# CP3.net
KiCad netlist of a schematic drawn in EAGLE
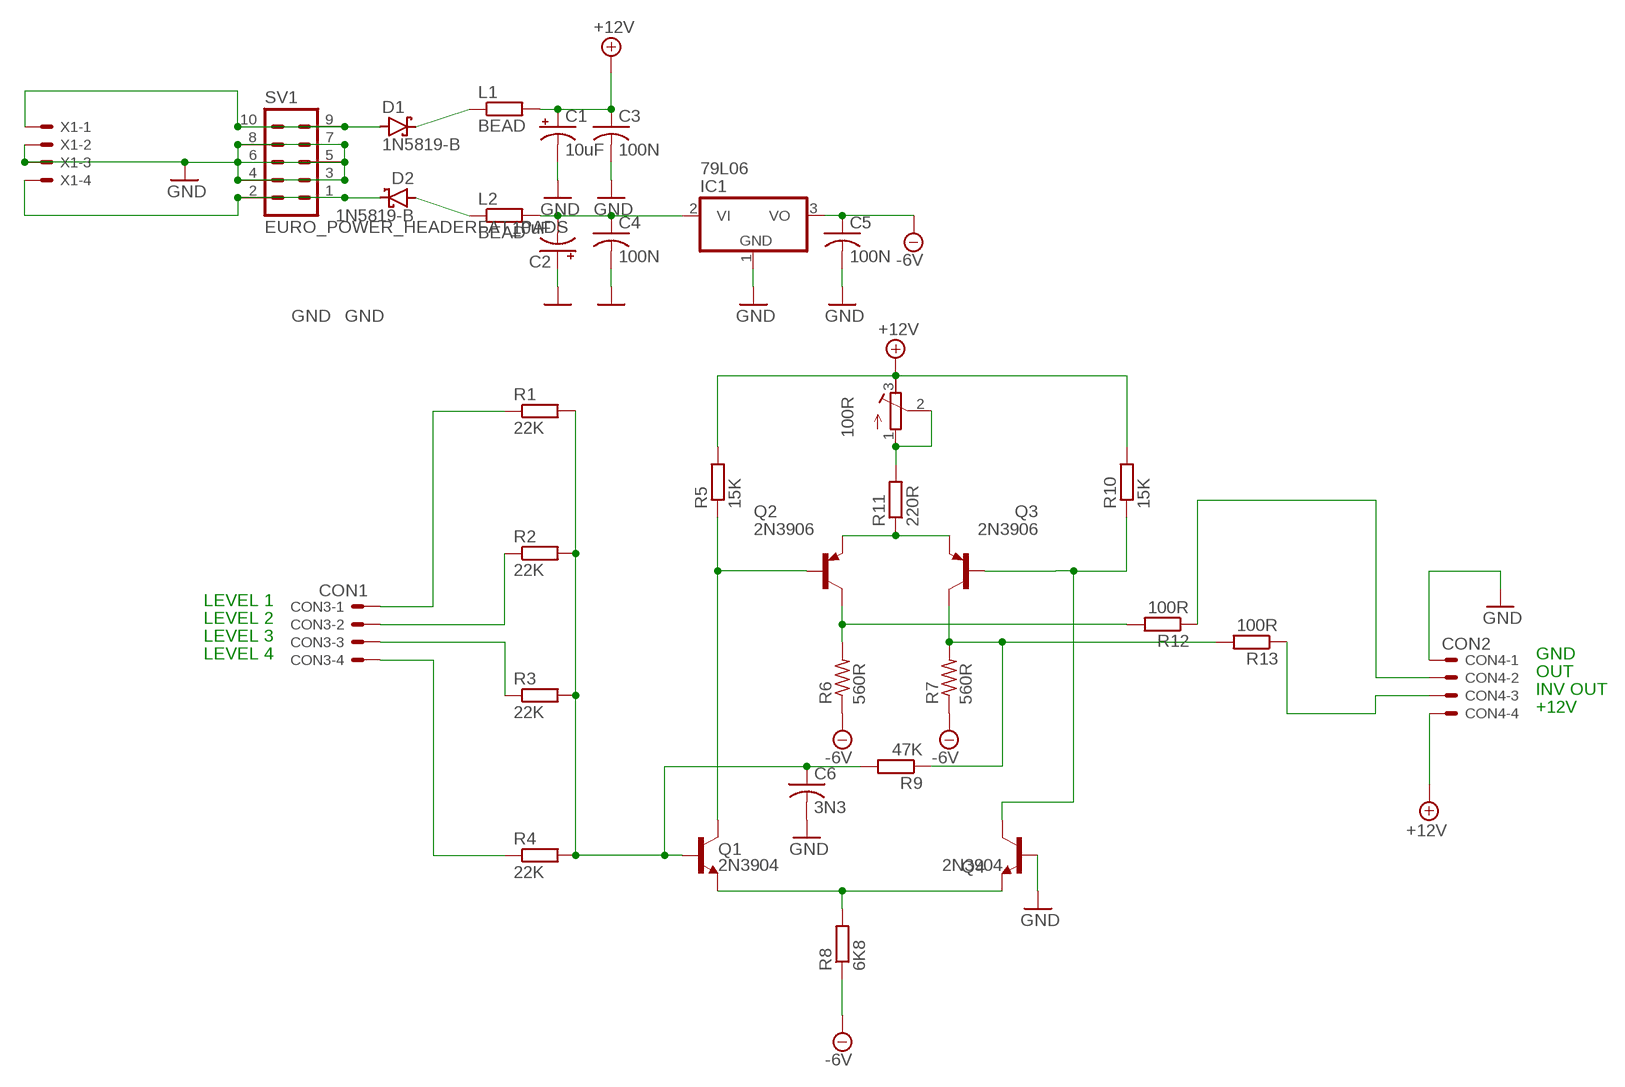
[diagram p0: schematic, sheet 1]

(export (version "E")
  (design (tool "Eeschema 10.0.6"))
  (components
    (comp (ref "100R")
      (value "R-TRIMM3296W")
      (footprint "eagle-import:RTRIM3296W")
      (libsource (lib "eagle-import") (part "R-TRIMM3296W"))
    )
    (comp (ref "C1")
      (value "10uF")
      (footprint "eagle-import:E2,5-7")
      (libsource (lib "eagle-import") (part "CPOL-USE2.5-7"))
    )
    (comp (ref "C2")
      (value "10uF")
      (footprint "eagle-import:E2,5-7")
      (libsource (lib "eagle-import") (part "CPOL-USE2.5-7"))
    )
    (comp (ref "C3")
      (value "100N")
      (footprint "eagle-import:C025-025X050")
      (libsource (lib "eagle-import") (part "C-US025-025X050"))
    )
    (comp (ref "C4")
      (value "100N")
      (footprint "eagle-import:C025-025X050")
      (libsource (lib "eagle-import") (part "C-US025-025X050"))
    )
    (comp (ref "C5")
      (value "100N")
      (footprint "eagle-import:C025-025X050")
      (libsource (lib "eagle-import") (part "C-US025-025X050"))
    )
    (comp (ref "C6")
      (value "3N3")
      (footprint "eagle-import:C025-025X050")
      (libsource (lib "eagle-import") (part "C-US025-025X050"))
    )
    (comp (ref "CON3")
      (value "CON1")
      (footprint "eagle-import:22-23-2041")
      (fields (field (name "MF") "MOLEX") (field (name "MPN") "22-23-2041"))
      (libsource (lib "eagle-import") (part "22-23-2041"))
    )
    (comp (ref "CON4")
      (value "CON2")
      (footprint "eagle-import:22-23-2041")
      (fields (field (name "MF") "MOLEX") (field (name "MPN") "22-23-2041"))
      (libsource (lib "eagle-import") (part "22-23-2041"))
    )
    (comp (ref "D1")
      (value "1N5819-B")
      (footprint "eagle-import:DO41-7.6")
      (libsource (lib "eagle-import") (part "1N5819-B"))
    )
    (comp (ref "D2")
      (value "1N5819-B")
      (footprint "eagle-import:DO41-7.6")
      (libsource (lib "eagle-import") (part "1N5819-B"))
    )
    (comp (ref "IC1")
      (value "79L06")
      (footprint "eagle-import:TO92")
      (libsource (lib "eagle-import") (part "79ZL12"))
    )
    (comp (ref "L1")
      (value "BEAD")
      (footprint "eagle-import:10MM_RESISTOR")
      (libsource (lib "eagle-import") (part "RESISTOR10MM_RESISTOR"))
    )
    (comp (ref "L2")
      (value "BEAD")
      (footprint "eagle-import:10MM_RESISTOR")
      (libsource (lib "eagle-import") (part "RESISTOR10MM_RESISTOR"))
    )
    (comp (ref "Q1")
      (value "2N3904")
      (footprint "eagle-import:TO-92")
      (libsource (lib "eagle-import") (part "TRANS_NPN-2N3904"))
    )
    (comp (ref "Q2")
      (value "2N3906")
      (footprint "eagle-import:TO92")
      (libsource (lib "eagle-import") (part "2N3906"))
    )
    (comp (ref "Q3")
      (value "2N3906")
      (footprint "eagle-import:TO92")
      (libsource (lib "eagle-import") (part "2N3906"))
    )
    (comp (ref "Q4")
      (value "2N3904")
      (footprint "eagle-import:TO-92")
      (libsource (lib "eagle-import") (part "TRANS_NPN-2N3904"))
    )
    (comp (ref "R1")
      (value "22K")
      (footprint "eagle-import:10MM_RESISTOR")
      (libsource (lib "eagle-import") (part "RESISTOR10MM_RESISTOR"))
    )
    (comp (ref "R2")
      (value "22K")
      (footprint "eagle-import:10MM_RESISTOR")
      (libsource (lib "eagle-import") (part "RESISTOR10MM_RESISTOR"))
    )
    (comp (ref "R3")
      (value "22K")
      (footprint "eagle-import:10MM_RESISTOR")
      (libsource (lib "eagle-import") (part "RESISTOR10MM_RESISTOR"))
    )
    (comp (ref "R4")
      (value "22K")
      (footprint "eagle-import:10MM_RESISTOR")
      (libsource (lib "eagle-import") (part "RESISTOR10MM_RESISTOR"))
    )
    (comp (ref "R5")
      (value "15K")
      (footprint "eagle-import:10MM_RESISTOR")
      (libsource (lib "eagle-import") (part "RESISTOR10MM_RESISTOR"))
    )
    (comp (ref "R6")
      (value "560R")
      (footprint "eagle-import:0207_12")
      (libsource (lib "eagle-import") (part "R-US_0207/12"))
    )
    (comp (ref "R7")
      (value "560R")
      (footprint "eagle-import:0207_12")
      (libsource (lib "eagle-import") (part "R-US_0207/12"))
    )
    (comp (ref "R8")
      (value "6K8")
      (footprint "eagle-import:10MM_RESISTOR")
      (libsource (lib "eagle-import") (part "RESISTOR10MM_RESISTOR"))
    )
    (comp (ref "R9")
      (value "47K")
      (footprint "eagle-import:10MM_RESISTOR")
      (libsource (lib "eagle-import") (part "RESISTOR10MM_RESISTOR"))
    )
    (comp (ref "R10")
      (value "15K")
      (footprint "eagle-import:10MM_RESISTOR")
      (libsource (lib "eagle-import") (part "RESISTOR10MM_RESISTOR"))
    )
    (comp (ref "R11")
      (value "220R")
      (footprint "eagle-import:10MM_RESISTOR")
      (libsource (lib "eagle-import") (part "RESISTOR10MM_RESISTOR"))
    )
    (comp (ref "R12")
      (value "100R")
      (footprint "eagle-import:10MM_RESISTOR")
      (libsource (lib "eagle-import") (part "RESISTOR10MM_RESISTOR"))
    )
    (comp (ref "R13")
      (value "100R")
      (footprint "eagle-import:10MM_RESISTOR")
      (libsource (lib "eagle-import") (part "RESISTOR10MM_RESISTOR"))
    )
    (comp (ref "SV1")
      (value "EURO_POWER_HEADERFAT_PADS")
      (footprint "eagle-import:EURO_PWR_HEADER_FAT")
      (libsource (lib "eagle-import") (part "EURO_POWER_HEADERFAT_PADS"))
    )
    (comp (ref "X1")
      (value "KK-156-4")
      (footprint "eagle-import:KK-156-4")
      (fields (field (name "MF") "MOLEX"))
      (libsource (lib "eagle-import") (part "KK-156-4"))
    )
  )
  (nets
    (net (code "1") (name "+12V") (class "Default")
      (node (ref "100R") (pin "3") (pinfunction "E_3") (pintype "passive"))
      (node (ref "C1") (pin "+") (pinfunction "+_+") (pintype "passive"))
      (node (ref "C3") (pin "1") (pinfunction "1_1") (pintype "passive"))
      (node (ref "CON4") (pin "4") (pinfunction "S_4") (pintype "passive"))
      (node (ref "L1") (pin "2") (pinfunction "2_2") (pintype "passive"))
      (node (ref "R10") (pin "2") (pinfunction "2_2") (pintype "passive"))
      (node (ref "R5") (pin "2") (pinfunction "2_2") (pintype "passive"))
    )
    (net (code "2") (name "-6V") (class "Default")
      (node (ref "C5") (pin "1") (pinfunction "1_1") (pintype "passive"))
      (node (ref "IC1") (pin "3") (pinfunction "VO_3") (pintype "passive"))
      (node (ref "R6") (pin "1") (pinfunction "1_1") (pintype "passive"))
      (node (ref "R7") (pin "1") (pinfunction "1_1") (pintype "passive"))
      (node (ref "R8") (pin "1") (pinfunction "1_1") (pintype "passive"))
    )
    (net (code "3") (name "GND") (class "Default")
      (node (ref "C1") (pin "-") (pinfunction "-_-") (pintype "passive"))
      (node (ref "C2") (pin "+") (pinfunction "+_+") (pintype "passive"))
      (node (ref "C3") (pin "2") (pinfunction "2_2") (pintype "passive"))
      (node (ref "C4") (pin "2") (pinfunction "2_2") (pintype "passive"))
      (node (ref "C5") (pin "2") (pinfunction "2_2") (pintype "passive"))
      (node (ref "C6") (pin "2") (pinfunction "2_2") (pintype "passive"))
      (node (ref "CON4") (pin "1") (pinfunction "S_1") (pintype "passive"))
      (node (ref "IC1") (pin "1") (pinfunction "GND_1") (pintype "passive"))
      (node (ref "Q4") (pin "2") (pinfunction "B_2") (pintype "passive"))
      (node (ref "SV1") (pin "3") (pinfunction "3_3") (pintype "passive"))
      (node (ref "SV1") (pin "4") (pinfunction "4_4") (pintype "passive"))
      (node (ref "SV1") (pin "5") (pinfunction "5_5") (pintype "passive"))
      (node (ref "SV1") (pin "6") (pinfunction "6_6") (pintype "passive"))
      (node (ref "SV1") (pin "7") (pinfunction "7_7") (pintype "passive"))
      (node (ref "SV1") (pin "8") (pinfunction "8_8") (pintype "passive"))
      (node (ref "X1") (pin "2") (pinfunction "S_2") (pintype "passive"))
      (node (ref "X1") (pin "3") (pinfunction "S_3") (pintype "passive"))
    )
    (net (code "4") (name "Net-(100R-A)") (class "Default")
      (node (ref "100R") (pin "1") (pinfunction "A_1") (pintype "passive"))
      (node (ref "100R") (pin "2") (pinfunction "S_2") (pintype "passive"))
      (node (ref "R11") (pin "2") (pinfunction "2_2") (pintype "passive"))
    )
    (net (code "5") (name "Net-(CON3A-S)") (class "Default")
      (node (ref "CON3") (pin "1") (pinfunction "S_1") (pintype "passive"))
      (node (ref "R1") (pin "1") (pinfunction "1_1") (pintype "passive"))
    )
    (net (code "6") (name "Net-(CON3B-S)") (class "Default")
      (node (ref "CON3") (pin "2") (pinfunction "S_2") (pintype "passive"))
      (node (ref "R2") (pin "1") (pinfunction "1_1") (pintype "passive"))
    )
    (net (code "7") (name "Net-(CON3C-S)") (class "Default")
      (node (ref "CON3") (pin "3") (pinfunction "S_3") (pintype "passive"))
      (node (ref "R3") (pin "1") (pinfunction "1_1") (pintype "passive"))
    )
    (net (code "8") (name "Net-(CON3D-S)") (class "Default")
      (node (ref "CON3") (pin "4") (pinfunction "S_4") (pintype "passive"))
      (node (ref "R4") (pin "1") (pinfunction "1_1") (pintype "passive"))
    )
    (net (code "9") (name "Net-(CON4B-S)") (class "Default")
      (node (ref "CON4") (pin "2") (pinfunction "S_2") (pintype "passive"))
      (node (ref "R12") (pin "1") (pinfunction "1_1") (pintype "passive"))
    )
    (net (code "10") (name "Net-(CON4C-S)") (class "Default")
      (node (ref "CON4") (pin "3") (pinfunction "S_3") (pintype "passive"))
      (node (ref "R13") (pin "1") (pinfunction "1_1") (pintype "passive"))
    )
    (net (code "11") (name "Net-(D1-PadC)") (class "Default")
      (node (ref "D1") (pin "C") (pinfunction "C_C") (pintype "passive"))
      (node (ref "L1") (pin "1") (pinfunction "1_1") (pintype "passive"))
    )
    (net (code "12") (name "Net-(D2-PadA)") (class "Default")
      (node (ref "D2") (pin "A") (pinfunction "A_A") (pintype "passive"))
      (node (ref "L2") (pin "1") (pinfunction "1_1") (pintype "passive"))
    )
    (net (code "13") (name "Net-(IC1-VI)") (class "Default")
      (node (ref "C2") (pin "-") (pinfunction "-_-") (pintype "passive"))
      (node (ref "C4") (pin "1") (pinfunction "1_1") (pintype "passive"))
      (node (ref "IC1") (pin "2") (pinfunction "VI_2") (pintype "input"))
      (node (ref "L2") (pin "2") (pinfunction "2_2") (pintype "passive"))
    )
    (net (code "14") (name "Net-(Q1-B)") (class "Default")
      (node (ref "C6") (pin "1") (pinfunction "1_1") (pintype "passive"))
      (node (ref "Q1") (pin "2") (pinfunction "B_2") (pintype "passive"))
      (node (ref "R1") (pin "2") (pinfunction "2_2") (pintype "passive"))
      (node (ref "R2") (pin "2") (pinfunction "2_2") (pintype "passive"))
      (node (ref "R3") (pin "2") (pinfunction "2_2") (pintype "passive"))
      (node (ref "R4") (pin "2") (pinfunction "2_2") (pintype "passive"))
      (node (ref "R9") (pin "2") (pinfunction "2_2") (pintype "passive"))
    )
    (net (code "15") (name "Net-(Q1-C)") (class "Default")
      (node (ref "Q1") (pin "3") (pinfunction "C_3") (pintype "passive"))
      (node (ref "Q2") (pin "2") (pinfunction "B_2") (pintype "passive"))
      (node (ref "R5") (pin "1") (pinfunction "1_1") (pintype "passive"))
    )
    (net (code "16") (name "Net-(Q1-E)") (class "Default")
      (node (ref "Q1") (pin "1") (pinfunction "E_1") (pintype "passive"))
      (node (ref "Q4") (pin "1") (pinfunction "E_1") (pintype "passive"))
      (node (ref "R8") (pin "2") (pinfunction "2_2") (pintype "passive"))
    )
    (net (code "17") (name "Net-(Q2-C)") (class "Default")
      (node (ref "Q2") (pin "1") (pinfunction "C_1") (pintype "passive"))
      (node (ref "R12") (pin "2") (pinfunction "2_2") (pintype "passive"))
      (node (ref "R6") (pin "2") (pinfunction "2_2") (pintype "passive"))
    )
    (net (code "18") (name "Net-(Q2-E)") (class "Default")
      (node (ref "Q2") (pin "3") (pinfunction "E_3") (pintype "passive"))
      (node (ref "Q3") (pin "3") (pinfunction "E_3") (pintype "passive"))
      (node (ref "R11") (pin "1") (pinfunction "1_1") (pintype "passive"))
    )
    (net (code "19") (name "Net-(Q3-B)") (class "Default")
      (node (ref "Q3") (pin "2") (pinfunction "B_2") (pintype "passive"))
      (node (ref "Q4") (pin "3") (pinfunction "C_3") (pintype "passive"))
      (node (ref "R10") (pin "1") (pinfunction "1_1") (pintype "passive"))
    )
    (net (code "20") (name "Net-(Q3-C)") (class "Default")
      (node (ref "Q3") (pin "1") (pinfunction "C_1") (pintype "passive"))
      (node (ref "R13") (pin "2") (pinfunction "2_2") (pintype "passive"))
      (node (ref "R7") (pin "2") (pinfunction "2_2") (pintype "passive"))
      (node (ref "R9") (pin "1") (pinfunction "1_1") (pintype "passive"))
    )
    (net (code "21") (name "Net-(X1A-S)") (class "Default")
      (node (ref "D1") (pin "A") (pinfunction "A_A") (pintype "passive"))
      (node (ref "SV1") (pin "10") (pinfunction "10_10") (pintype "passive"))
      (node (ref "SV1") (pin "9") (pinfunction "9_9") (pintype "passive"))
      (node (ref "X1") (pin "1") (pinfunction "S_1") (pintype "passive"))
    )
    (net (code "22") (name "Net-(X1D-S)") (class "Default")
      (node (ref "D2") (pin "C") (pinfunction "C_C") (pintype "passive"))
      (node (ref "SV1") (pin "1") (pinfunction "1_1") (pintype "passive"))
      (node (ref "SV1") (pin "2") (pinfunction "2_2") (pintype "passive"))
      (node (ref "X1") (pin "4") (pinfunction "S_4") (pintype "passive"))
    )
  )
)
